# Encoder.net
KiCad netlist of a schematic drawn in Altium Designer
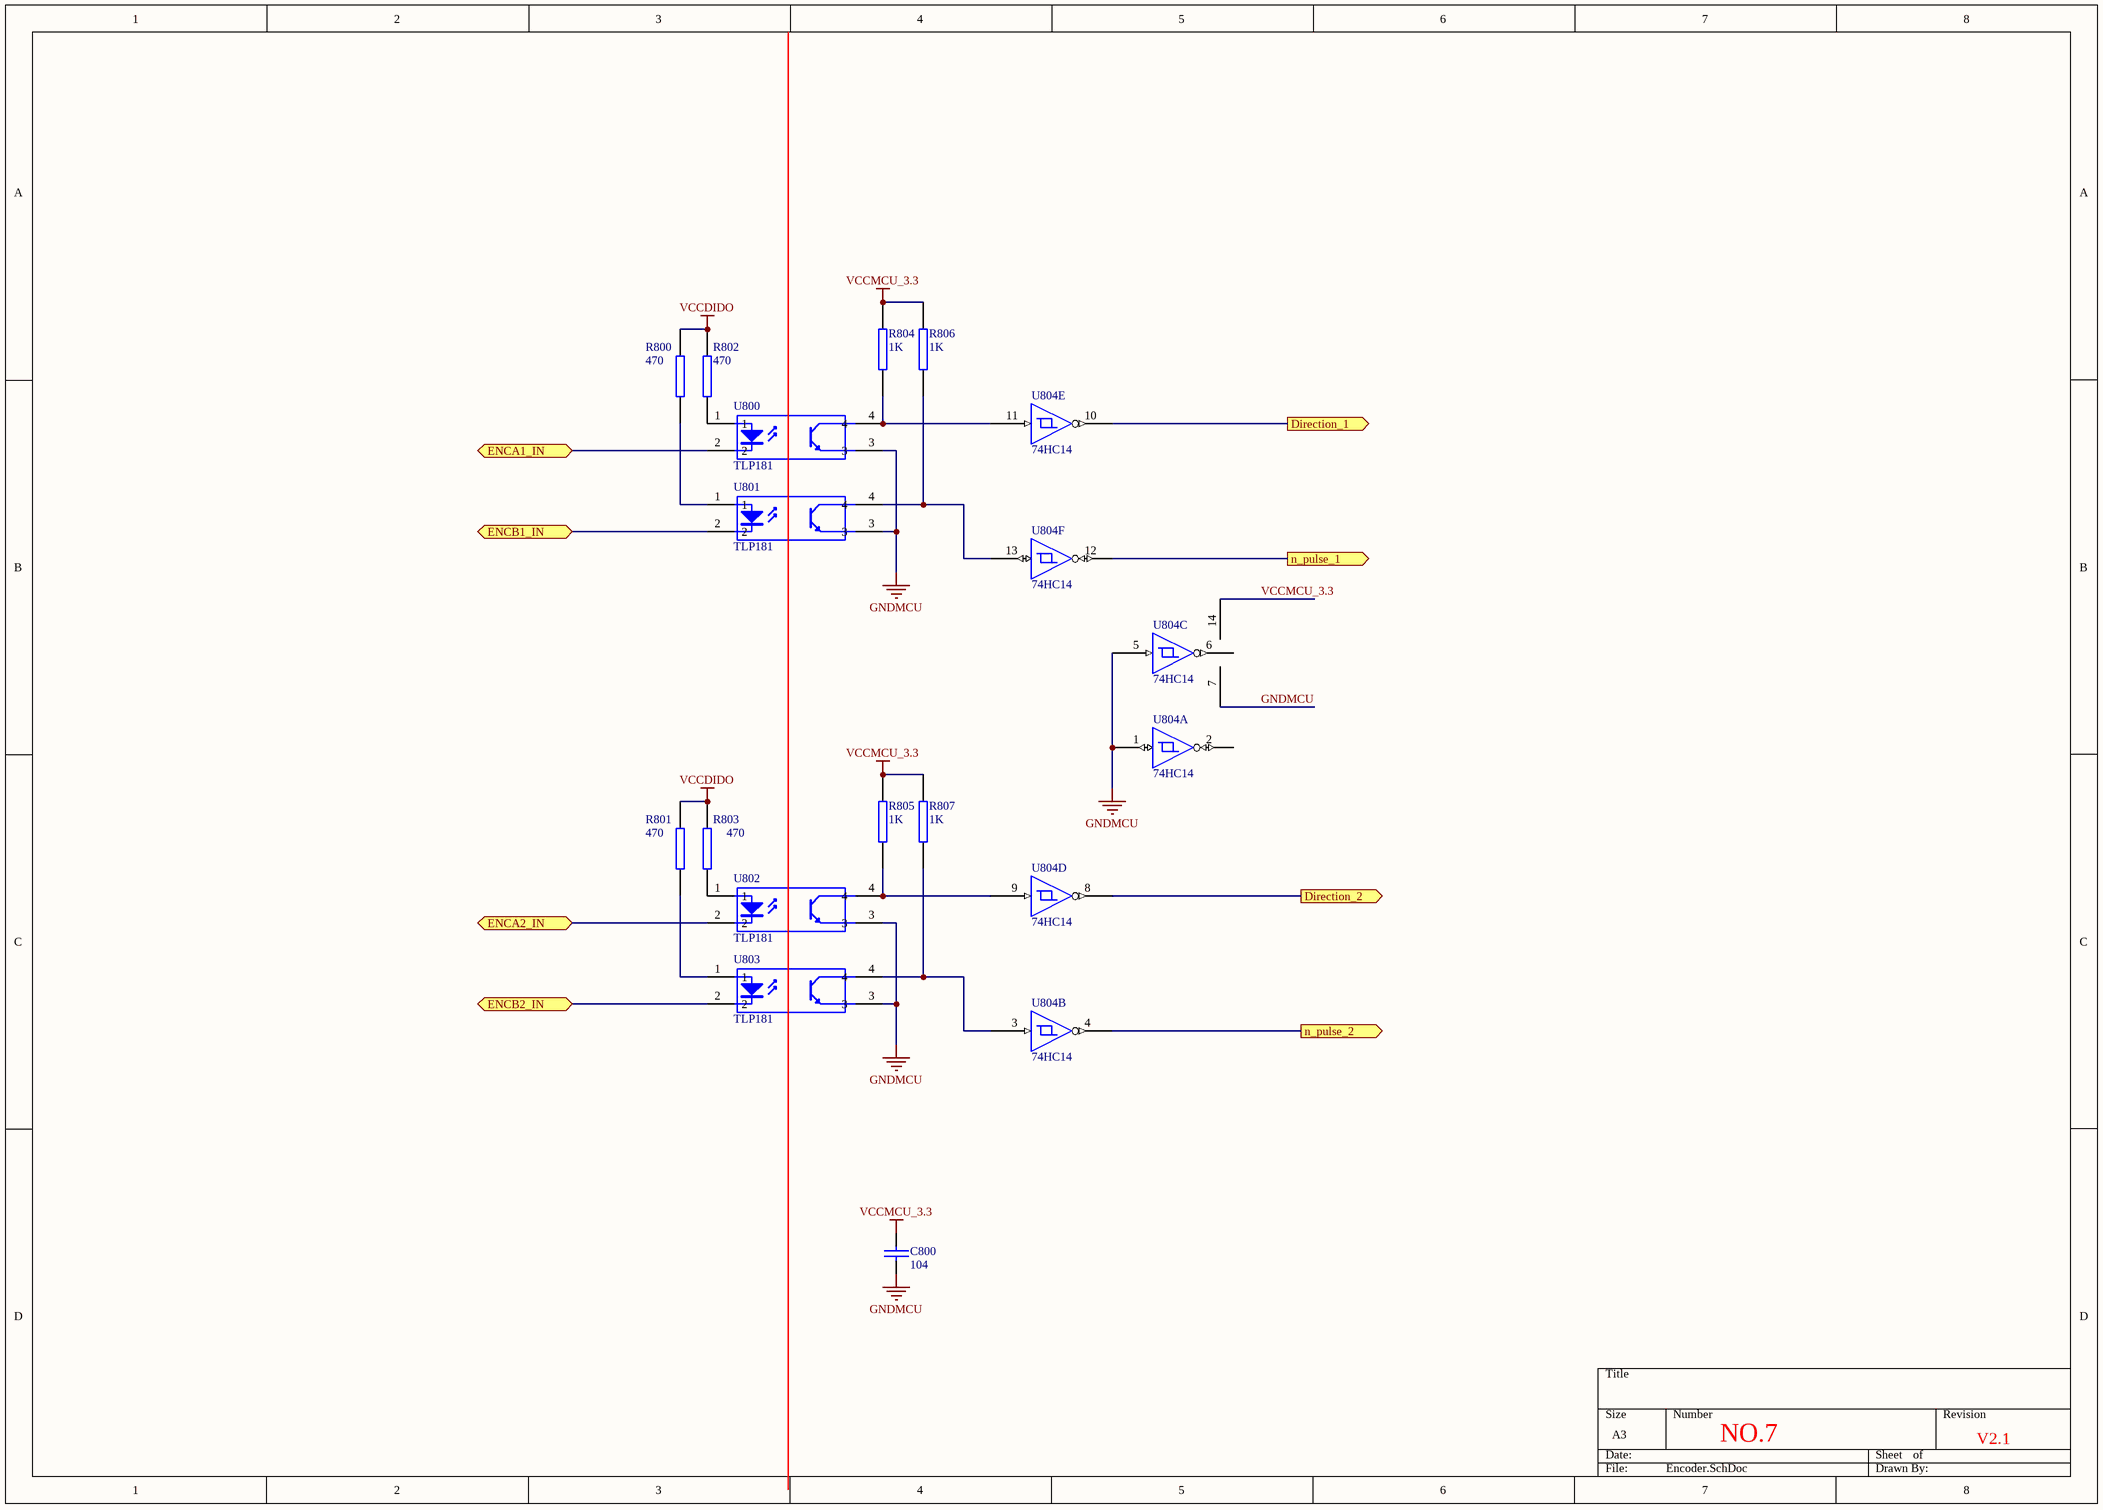
[diagram p0: Encoder.SchDoc]

(export (version "E")
  (design (tool "Eeschema 10.0.6"))
  (components
    (comp (ref "C800")
      (value "104")
      (footprint "CAPC_E0805_2012X70N")
      (description "Capacitor")
      (libsource (lib "YGInfoSCHLib") (part "CAP"))
    )
    (comp (ref "R800")
      (value "470")
      (footprint "RESC_E0805_2012X50N")
      (libsource (lib "YGInfoSCHLib") (part "RES2"))
    )
    (comp (ref "R801")
      (value "470")
      (footprint "RESC_E0805_2012X50N")
      (libsource (lib "YGInfoSCHLib") (part "RES2"))
    )
    (comp (ref "R802")
      (value "470")
      (footprint "RESC_E0805_2012X50N")
      (libsource (lib "YGInfoSCHLib") (part "RES2"))
    )
    (comp (ref "R803")
      (value "470")
      (footprint "RESC_E0805_2012X50N")
      (libsource (lib "YGInfoSCHLib") (part "RES2"))
    )
    (comp (ref "R804")
      (value "1K")
      (footprint "RESC_E0805_2012X50N")
      (libsource (lib "YGInfoSCHLib") (part "RES2"))
    )
    (comp (ref "R805")
      (value "1K")
      (footprint "RESC_E0805_2012X50N")
      (libsource (lib "YGInfoSCHLib") (part "RES2"))
    )
    (comp (ref "R806")
      (value "1K")
      (footprint "RESC_E0805_2012X50N")
      (libsource (lib "YGInfoSCHLib") (part "RES2"))
    )
    (comp (ref "R807")
      (value "1K")
      (footprint "RESC_E0805_2012X50N")
      (libsource (lib "YGInfoSCHLib") (part "RES2"))
    )
    (comp (ref "U800")
      (value "TLP181")
      (footprint "TLP181")
      (description "光耦隔离")
      (libsource (lib "YGInfoSCHLib") (part "TLP181"))
    )
    (comp (ref "U801")
      (value "TLP181")
      (footprint "TLP181")
      (description "光耦隔离")
      (libsource (lib "YGInfoSCHLib") (part "TLP181"))
    )
    (comp (ref "U802")
      (value "TLP181")
      (footprint "TLP181")
      (description "光耦隔离")
      (libsource (lib "YGInfoSCHLib") (part "TLP181"))
    )
    (comp (ref "U803")
      (value "TLP181")
      (footprint "TLP181")
      (description "光耦隔离")
      (libsource (lib "YGInfoSCHLib") (part "TLP181"))
    )
    (comp (ref "U804") (value "74HC14") (footprint "SO-14") (libsource (lib "") (part "74LS14_2")))
  )
  (nets
    (net (code "1") (name "/Direction_1") (class "Default") (node (ref "U804") (pin "10") (pintype "output")))
    (net (code "2") (name "/Direction_2") (class "Default") (node (ref "U804") (pin "8") (pintype "output")))
    (net (code "3") (name "/ENCA1_IN") (class "Default")
      (node (ref "U800") (pin "2") (pinfunction "2_2") (pintype "passive"))
    )
    (net (code "4") (name "/ENCA2_IN") (class "Default")
      (node (ref "U802") (pin "2") (pinfunction "2_2") (pintype "passive"))
    )
    (net (code "5") (name "/ENCB1_IN") (class "Default")
      (node (ref "U801") (pin "2") (pinfunction "2_2") (pintype "passive"))
    )
    (net (code "6") (name "/ENCB2_IN") (class "Default")
      (node (ref "U803") (pin "2") (pinfunction "2_2") (pintype "passive"))
    )
    (net (code "7") (name "/n_pulse_1") (class "Default")
      (node (ref "U804") (pin "12") (pintype "bidirectional"))
    )
    (net (code "8") (name "/n_pulse_2") (class "Default") (node (ref "U804") (pin "4") (pintype "output")))
    (net (code "9") (name "GNDMCU") (class "Default")
      (node (ref "C800") (pin "2") (pinfunction "2_2") (pintype "passive"))
      (node (ref "U800") (pin "3") (pinfunction "3_3") (pintype "passive"))
      (node (ref "U801") (pin "3") (pinfunction "3_3") (pintype "passive"))
      (node (ref "U802") (pin "3") (pinfunction "3_3") (pintype "passive"))
      (node (ref "U803") (pin "3") (pinfunction "3_3") (pintype "passive"))
      (node (ref "U804") (pin "1") (pintype "bidirectional"))
      (node (ref "U804") (pin "5") (pintype "input"))
      (node (ref "U804") (pin "7") (pintype "power_in"))
    )
    (net (code "10") (name "Net-(R800-Pad2)") (class "Default")
      (node (ref "R800") (pin "2") (pinfunction "2_2") (pintype "passive"))
      (node (ref "U801") (pin "1") (pinfunction "1_1") (pintype "passive"))
    )
    (net (code "11") (name "Net-(R801-Pad1)") (class "Default")
      (node (ref "R801") (pin "1") (pinfunction "1_1") (pintype "passive"))
      (node (ref "U803") (pin "1") (pinfunction "1_1") (pintype "passive"))
    )
    (net (code "12") (name "Net-(R802-Pad1)") (class "Default")
      (node (ref "R802") (pin "1") (pinfunction "1_1") (pintype "passive"))
      (node (ref "U800") (pin "1") (pinfunction "1_1") (pintype "passive"))
    )
    (net (code "13") (name "Net-(R803-Pad2)") (class "Default")
      (node (ref "R803") (pin "2") (pinfunction "2_2") (pintype "passive"))
      (node (ref "U802") (pin "1") (pinfunction "1_1") (pintype "passive"))
    )
    (net (code "14") (name "Net-(R804-Pad2)") (class "Default")
      (node (ref "R804") (pin "2") (pinfunction "2_2") (pintype "passive"))
      (node (ref "U800") (pin "4") (pinfunction "4_4") (pintype "passive"))
      (node (ref "U804") (pin "11") (pintype "input"))
    )
    (net (code "15") (name "Net-(R805-Pad2)") (class "Default")
      (node (ref "R805") (pin "2") (pinfunction "2_2") (pintype "passive"))
      (node (ref "U802") (pin "4") (pinfunction "4_4") (pintype "passive"))
      (node (ref "U804") (pin "9") (pintype "input"))
    )
    (net (code "16") (name "Net-(R806-Pad2)") (class "Default")
      (node (ref "R806") (pin "2") (pinfunction "2_2") (pintype "passive"))
      (node (ref "U801") (pin "4") (pinfunction "4_4") (pintype "passive"))
      (node (ref "U804") (pin "13") (pintype "bidirectional"))
    )
    (net (code "17") (name "Net-(R807-Pad2)") (class "Default")
      (node (ref "R807") (pin "2") (pinfunction "2_2") (pintype "passive"))
      (node (ref "U803") (pin "4") (pinfunction "4_4") (pintype "passive"))
      (node (ref "U804") (pin "3") (pintype "input"))
    )
    (net (code "18") (name "VCCDIDO") (class "Default")
      (node (ref "R800") (pin "1") (pinfunction "1_1") (pintype "passive"))
      (node (ref "R801") (pin "2") (pinfunction "2_2") (pintype "passive"))
      (node (ref "R802") (pin "2") (pinfunction "2_2") (pintype "passive"))
      (node (ref "R803") (pin "1") (pinfunction "1_1") (pintype "passive"))
    )
    (net (code "19") (name "VCCMCU_3.3") (class "Default")
      (node (ref "C800") (pin "1") (pinfunction "1_1") (pintype "passive"))
      (node (ref "R804") (pin "1") (pinfunction "1_1") (pintype "passive"))
      (node (ref "R805") (pin "1") (pinfunction "1_1") (pintype "passive"))
      (node (ref "R806") (pin "1") (pinfunction "1_1") (pintype "passive"))
      (node (ref "R807") (pin "1") (pinfunction "1_1") (pintype "passive"))
      (node (ref "U804") (pin "14") (pintype "power_in"))
    )
    (net (code "20") (name "unconnected-(U804-Pad2)") (class "Default")
      (node (ref "U804") (pin "2") (pintype "bidirectional"))
    )
    (net (code "21") (name "unconnected-(U804-Pad6)") (class "Default")
      (node (ref "U804") (pin "6") (pintype "output"))
    )
  )
)
